# M103A.net
KiCad netlist of a schematic drawn in EAGLE
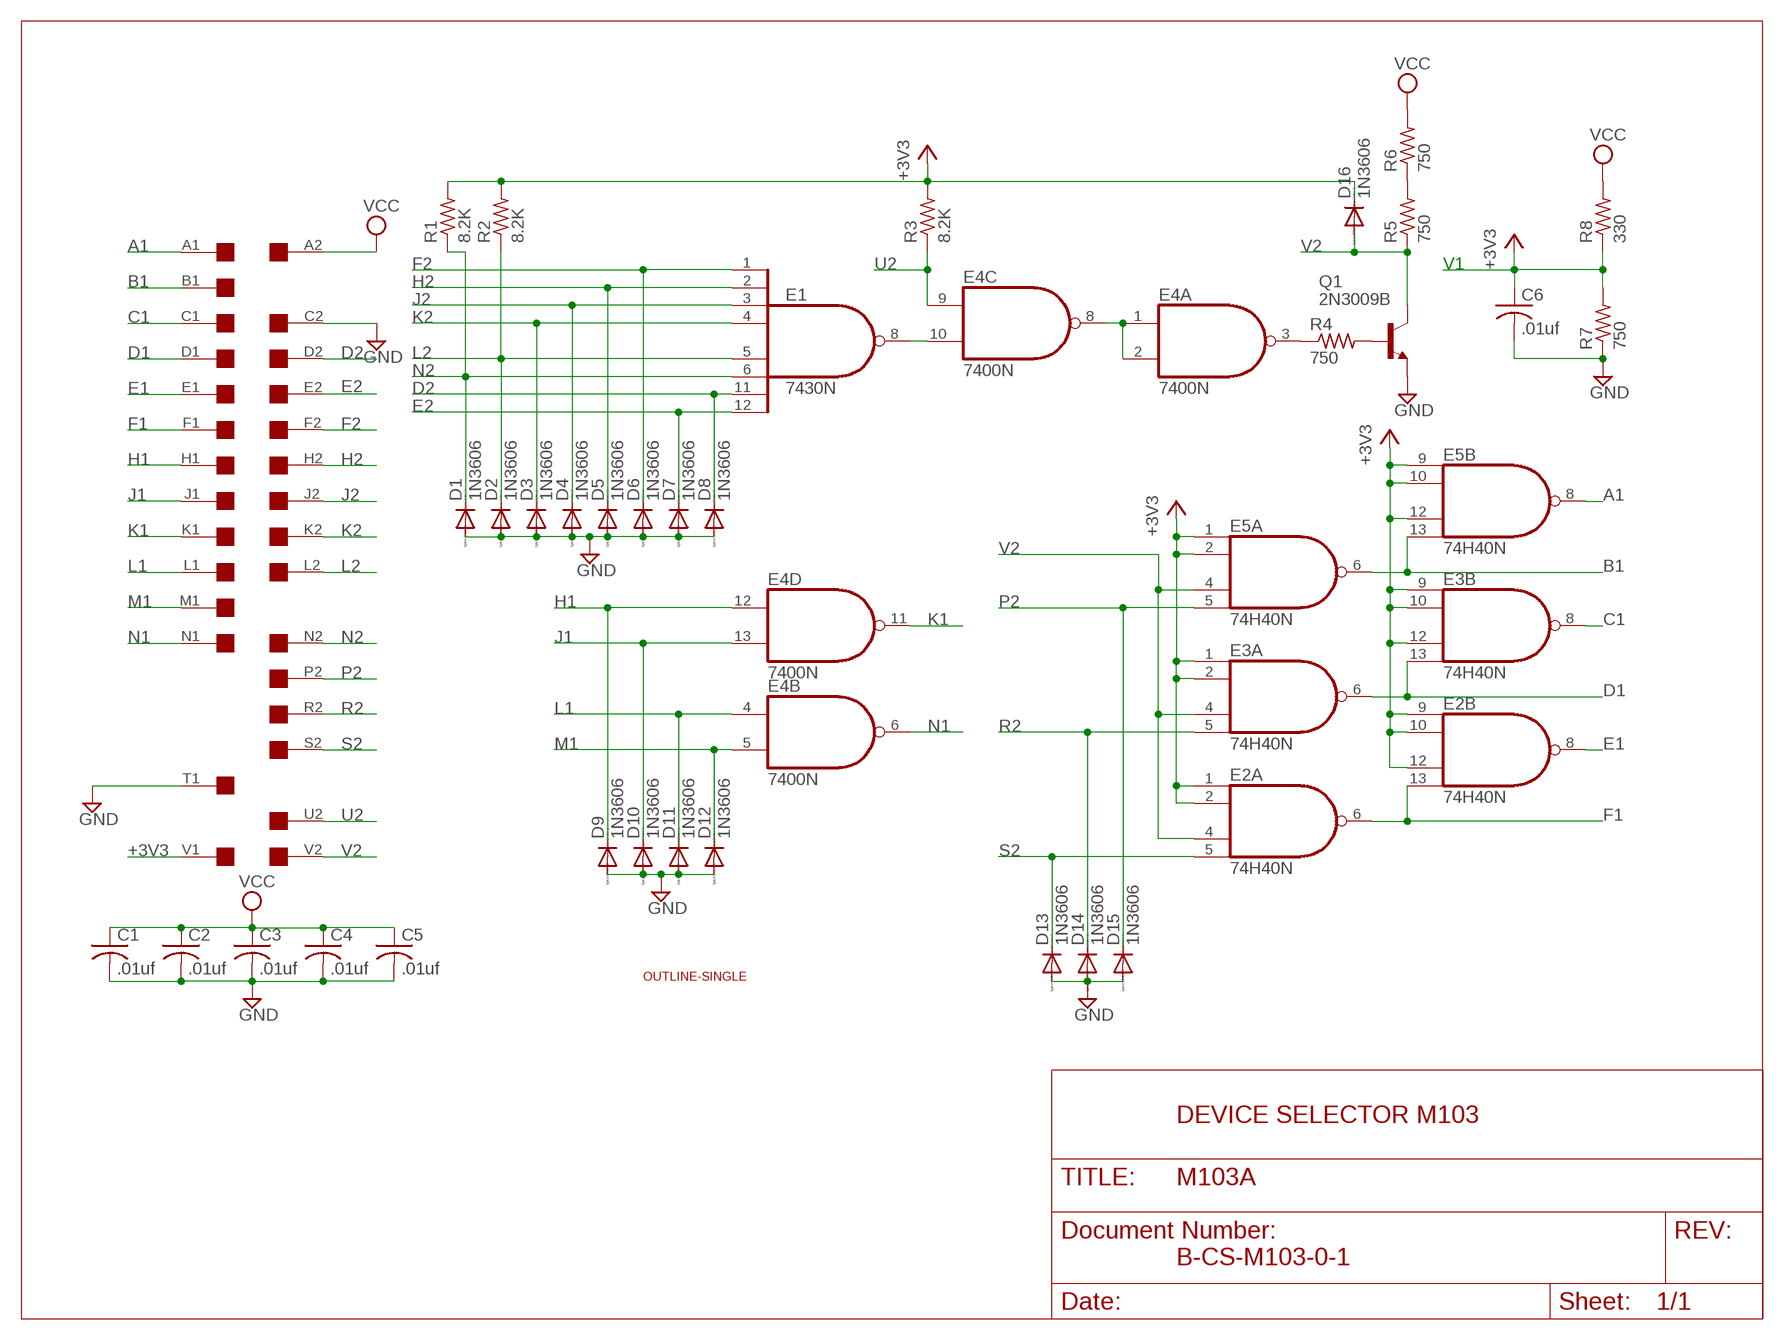
[diagram p0: schematic, sheet 1]

(export (version "E")
  (design (tool "Eeschema 10.0.6"))
  (components
    (comp (ref "C1")
      (value ".01uf")
      (footprint "eagle-import:C050-025X075")
      (libsource (lib "eagle-import") (part "C-US050-025X075"))
    )
    (comp (ref "C2")
      (value ".01uf")
      (footprint "eagle-import:C050-025X075")
      (libsource (lib "eagle-import") (part "C-US050-025X075"))
    )
    (comp (ref "C3")
      (value ".01uf")
      (footprint "eagle-import:C050-025X075")
      (libsource (lib "eagle-import") (part "C-US050-025X075"))
    )
    (comp (ref "C4")
      (value ".01uf")
      (footprint "eagle-import:C050-025X075")
      (libsource (lib "eagle-import") (part "C-US050-025X075"))
    )
    (comp (ref "C5")
      (value ".01uf")
      (footprint "eagle-import:C050-025X075")
      (libsource (lib "eagle-import") (part "C-US050-025X075"))
    )
    (comp (ref "C6")
      (value ".01uf")
      (footprint "eagle-import:C050-025X075")
      (libsource (lib "eagle-import") (part "C-US050-025X075"))
    )
    (comp (ref "D1")
      (value "1N3606")
      (footprint "eagle-import:DO35-10")
      (libsource (lib "eagle-import") (part "1N4148DO35-10"))
    )
    (comp (ref "D2")
      (value "1N3606")
      (footprint "eagle-import:DO35-10")
      (libsource (lib "eagle-import") (part "1N4148DO35-10"))
    )
    (comp (ref "D3")
      (value "1N3606")
      (footprint "eagle-import:DO35-10")
      (libsource (lib "eagle-import") (part "1N4148DO35-10"))
    )
    (comp (ref "D4")
      (value "1N3606")
      (footprint "eagle-import:DO35-10")
      (libsource (lib "eagle-import") (part "1N4148DO35-10"))
    )
    (comp (ref "D5")
      (value "1N3606")
      (footprint "eagle-import:DO35-10")
      (libsource (lib "eagle-import") (part "1N4148DO35-10"))
    )
    (comp (ref "D6")
      (value "1N3606")
      (footprint "eagle-import:DO35-10")
      (libsource (lib "eagle-import") (part "1N4148DO35-10"))
    )
    (comp (ref "D7")
      (value "1N3606")
      (footprint "eagle-import:DO35-10")
      (libsource (lib "eagle-import") (part "1N4148DO35-10"))
    )
    (comp (ref "D8")
      (value "1N3606")
      (footprint "eagle-import:DO35-10")
      (libsource (lib "eagle-import") (part "1N4148DO35-10"))
    )
    (comp (ref "D9")
      (value "1N3606")
      (footprint "eagle-import:DO35-10")
      (libsource (lib "eagle-import") (part "1N4148DO35-10"))
    )
    (comp (ref "D10")
      (value "1N3606")
      (footprint "eagle-import:DO35-10")
      (libsource (lib "eagle-import") (part "1N4148DO35-10"))
    )
    (comp (ref "D11")
      (value "1N3606")
      (footprint "eagle-import:DO35-10")
      (libsource (lib "eagle-import") (part "1N4148DO35-10"))
    )
    (comp (ref "D12")
      (value "1N3606")
      (footprint "eagle-import:DO35-10")
      (libsource (lib "eagle-import") (part "1N4148DO35-10"))
    )
    (comp (ref "D13")
      (value "1N3606")
      (footprint "eagle-import:DO35-10")
      (libsource (lib "eagle-import") (part "1N4148DO35-10"))
    )
    (comp (ref "D14")
      (value "1N3606")
      (footprint "eagle-import:DO35-10")
      (libsource (lib "eagle-import") (part "1N4148DO35-10"))
    )
    (comp (ref "D15")
      (value "1N3606")
      (footprint "eagle-import:DO35-10")
      (libsource (lib "eagle-import") (part "1N4148DO35-10"))
    )
    (comp (ref "D16")
      (value "1N3606")
      (footprint "eagle-import:DO35-10")
      (libsource (lib "eagle-import") (part "1N4148DO35-10"))
    )
    (comp (ref "E1")
      (value "7430N")
      (footprint "eagle-import:DIL14")
      (libsource (lib "eagle-import") (part "7430N"))
    )
    (comp (ref "E2")
      (value "74H40N")
      (footprint "eagle-import:DIL14")
      (libsource (lib "eagle-import") (part "7420NS"))
    )
    (comp (ref "E3")
      (value "74H40N")
      (footprint "eagle-import:DIL14")
      (libsource (lib "eagle-import") (part "7420NS"))
    )
    (comp (ref "E4")
      (value "7400N")
      (footprint "eagle-import:DIL14")
      (libsource (lib "eagle-import") (part "7400N"))
    )
    (comp (ref "E5")
      (value "74H40N")
      (footprint "eagle-import:DIL14")
      (libsource (lib "eagle-import") (part "7420NS"))
    )
    (comp (ref "Q1")
      (value "2N3009B")
      (footprint "eagle-import:TO39")
      (libsource (lib "eagle-import") (part "-NPN-TO39-EBC2N1613"))
    )
    (comp (ref "R1")
      (value "8.2K")
      (footprint "eagle-import:0207_10")
      (libsource (lib "eagle-import") (part "R-US_0207/10"))
    )
    (comp (ref "R2")
      (value "8.2K")
      (footprint "eagle-import:0207_10")
      (libsource (lib "eagle-import") (part "R-US_0207/10"))
    )
    (comp (ref "R3")
      (value "8.2K")
      (footprint "eagle-import:0207_10")
      (libsource (lib "eagle-import") (part "R-US_0207/10"))
    )
    (comp (ref "R4")
      (value "750")
      (footprint "eagle-import:0207_10")
      (libsource (lib "eagle-import") (part "R-US_0207/10"))
    )
    (comp (ref "R5")
      (value "750")
      (footprint "eagle-import:0207_10")
      (libsource (lib "eagle-import") (part "R-US_0207/10"))
    )
    (comp (ref "R6")
      (value "750")
      (footprint "eagle-import:0207_10")
      (libsource (lib "eagle-import") (part "R-US_0207/10"))
    )
    (comp (ref "R7")
      (value "750")
      (footprint "eagle-import:0207_10")
      (libsource (lib "eagle-import") (part "R-US_0207/10"))
    )
    (comp (ref "R8")
      (value "330")
      (footprint "eagle-import:0207_10")
      (libsource (lib "eagle-import") (part "R-US_0207/10"))
    )
    (comp (ref "U$8")
      (value "SINGLE")
      (footprint "eagle-import:EDGE-CON2")
      (libsource (lib "eagle-import") (part "SINGLE"))
    )
    (comp (ref "U$9")
      (value "OUTLINE-SINGLE")
      (footprint "eagle-import:SINGLE")
      (libsource (lib "eagle-import") (part "OUTLINE-SINGLE"))
    )
  )
  (nets
    (net (code "1") (name "+3V3") (class "Default")
      (node (ref "C6") (pin "1") (pinfunction "1_1") (pintype "passive"))
      (node (ref "D16") (pin "C") (pinfunction "C_C") (pintype "passive"))
      (node (ref "E2") (pin "1") (pinfunction "I0_1") (pintype "input"))
      (node (ref "E2") (pin "10") (pinfunction "I1_10") (pintype "input"))
      (node (ref "E2") (pin "12") (pinfunction "I2_12") (pintype "input"))
      (node (ref "E2") (pin "2") (pinfunction "I1_2") (pintype "input"))
      (node (ref "E2") (pin "9") (pinfunction "I0_9") (pintype "input"))
      (node (ref "E3") (pin "1") (pinfunction "I0_1") (pintype "input"))
      (node (ref "E3") (pin "10") (pinfunction "I1_10") (pintype "input"))
      (node (ref "E3") (pin "12") (pinfunction "I2_12") (pintype "input"))
      (node (ref "E3") (pin "2") (pinfunction "I1_2") (pintype "input"))
      (node (ref "E3") (pin "9") (pinfunction "I0_9") (pintype "input"))
      (node (ref "E5") (pin "1") (pinfunction "I0_1") (pintype "input"))
      (node (ref "E5") (pin "10") (pinfunction "I1_10") (pintype "input"))
      (node (ref "E5") (pin "12") (pinfunction "I2_12") (pintype "input"))
      (node (ref "E5") (pin "2") (pinfunction "I1_2") (pintype "input"))
      (node (ref "E5") (pin "9") (pinfunction "I0_9") (pintype "input"))
      (node (ref "R1") (pin "2") (pinfunction "2_2") (pintype "passive"))
      (node (ref "R2") (pin "2") (pinfunction "2_2") (pintype "passive"))
      (node (ref "R3") (pin "2") (pinfunction "2_2") (pintype "passive"))
      (node (ref "R7") (pin "2") (pinfunction "2_2") (pintype "passive"))
      (node (ref "R8") (pin "1") (pinfunction "1_1") (pintype "passive"))
      (node (ref "U$8") (pin "V1") (pinfunction "1_V1") (pintype "bidirectional"))
    )
    (net (code "2") (name "/A1") (class "Default")
      (node (ref "E5") (pin "8") (pinfunction "O_8") (pintype "output"))
      (node (ref "U$8") (pin "A1") (pinfunction "1_A1") (pintype "bidirectional"))
    )
    (net (code "3") (name "/B1") (class "Default")
      (node (ref "E5") (pin "13") (pinfunction "I3_13") (pintype "input"))
      (node (ref "E5") (pin "6") (pinfunction "O_6") (pintype "output"))
      (node (ref "U$8") (pin "B1") (pinfunction "1_B1") (pintype "bidirectional"))
    )
    (net (code "4") (name "/C1") (class "Default")
      (node (ref "E3") (pin "8") (pinfunction "O_8") (pintype "output"))
      (node (ref "U$8") (pin "C1") (pinfunction "1_C1") (pintype "bidirectional"))
    )
    (net (code "5") (name "/D1") (class "Default")
      (node (ref "E3") (pin "13") (pinfunction "I3_13") (pintype "input"))
      (node (ref "E3") (pin "6") (pinfunction "O_6") (pintype "output"))
      (node (ref "U$8") (pin "D1") (pinfunction "1_D1") (pintype "bidirectional"))
    )
    (net (code "6") (name "/D2") (class "Default")
      (node (ref "D8") (pin "C") (pinfunction "C_C") (pintype "passive"))
      (node (ref "E1") (pin "11") (pinfunction "I6_11") (pintype "input"))
      (node (ref "U$8") (pin "D2") (pinfunction "1_D2") (pintype "bidirectional"))
    )
    (net (code "7") (name "/E1") (class "Default")
      (node (ref "E2") (pin "8") (pinfunction "O_8") (pintype "output"))
      (node (ref "U$8") (pin "E1") (pinfunction "1_E1") (pintype "bidirectional"))
    )
    (net (code "8") (name "/E2") (class "Default")
      (node (ref "D7") (pin "C") (pinfunction "C_C") (pintype "passive"))
      (node (ref "E1") (pin "12") (pinfunction "I7_12") (pintype "input"))
      (node (ref "U$8") (pin "E2") (pinfunction "1_E2") (pintype "bidirectional"))
    )
    (net (code "9") (name "/F1") (class "Default")
      (node (ref "E2") (pin "13") (pinfunction "I3_13") (pintype "input"))
      (node (ref "E2") (pin "6") (pinfunction "O_6") (pintype "output"))
      (node (ref "U$8") (pin "F1") (pinfunction "1_F1") (pintype "bidirectional"))
    )
    (net (code "10") (name "/F2") (class "Default")
      (node (ref "D6") (pin "C") (pinfunction "C_C") (pintype "passive"))
      (node (ref "E1") (pin "1") (pinfunction "I0_1") (pintype "input"))
      (node (ref "U$8") (pin "F2") (pinfunction "1_F2") (pintype "bidirectional"))
    )
    (net (code "11") (name "/H1") (class "Default")
      (node (ref "D9") (pin "C") (pinfunction "C_C") (pintype "passive"))
      (node (ref "E4") (pin "12") (pinfunction "I0_12") (pintype "input"))
      (node (ref "U$8") (pin "H1") (pinfunction "1_H1") (pintype "bidirectional"))
    )
    (net (code "12") (name "/H2") (class "Default")
      (node (ref "D5") (pin "C") (pinfunction "C_C") (pintype "passive"))
      (node (ref "E1") (pin "2") (pinfunction "I1_2") (pintype "input"))
      (node (ref "U$8") (pin "H2") (pinfunction "1_H2") (pintype "bidirectional"))
    )
    (net (code "13") (name "/J1") (class "Default")
      (node (ref "D10") (pin "C") (pinfunction "C_C") (pintype "passive"))
      (node (ref "E4") (pin "13") (pinfunction "I1_13") (pintype "input"))
      (node (ref "U$8") (pin "J1") (pinfunction "1_J1") (pintype "bidirectional"))
    )
    (net (code "14") (name "/J2") (class "Default")
      (node (ref "D4") (pin "C") (pinfunction "C_C") (pintype "passive"))
      (node (ref "E1") (pin "3") (pinfunction "I2_3") (pintype "input"))
      (node (ref "U$8") (pin "J2") (pinfunction "1_J2") (pintype "bidirectional"))
    )
    (net (code "15") (name "/K1") (class "Default")
      (node (ref "E4") (pin "11") (pinfunction "O_11") (pintype "output"))
      (node (ref "U$8") (pin "K1") (pinfunction "1_K1") (pintype "bidirectional"))
    )
    (net (code "16") (name "/K2") (class "Default")
      (node (ref "D3") (pin "C") (pinfunction "C_C") (pintype "passive"))
      (node (ref "E1") (pin "4") (pinfunction "I3_4") (pintype "input"))
      (node (ref "U$8") (pin "K2") (pinfunction "1_K2") (pintype "bidirectional"))
    )
    (net (code "17") (name "/L1") (class "Default")
      (node (ref "D11") (pin "C") (pinfunction "C_C") (pintype "passive"))
      (node (ref "E4") (pin "4") (pinfunction "I0_4") (pintype "input"))
      (node (ref "U$8") (pin "L1") (pinfunction "1_L1") (pintype "bidirectional"))
    )
    (net (code "18") (name "/L2") (class "Default")
      (node (ref "D2") (pin "C") (pinfunction "C_C") (pintype "passive"))
      (node (ref "E1") (pin "5") (pinfunction "I4_5") (pintype "input"))
      (node (ref "R2") (pin "1") (pinfunction "1_1") (pintype "passive"))
      (node (ref "U$8") (pin "L2") (pinfunction "1_L2") (pintype "bidirectional"))
    )
    (net (code "19") (name "/M1") (class "Default")
      (node (ref "D12") (pin "C") (pinfunction "C_C") (pintype "passive"))
      (node (ref "E4") (pin "5") (pinfunction "I1_5") (pintype "input"))
      (node (ref "U$8") (pin "M1") (pinfunction "1_M1") (pintype "bidirectional"))
    )
    (net (code "20") (name "/N1") (class "Default")
      (node (ref "E4") (pin "6") (pinfunction "O_6") (pintype "output"))
      (node (ref "U$8") (pin "N1") (pinfunction "1_N1") (pintype "bidirectional"))
    )
    (net (code "21") (name "/N2") (class "Default")
      (node (ref "D1") (pin "C") (pinfunction "C_C") (pintype "passive"))
      (node (ref "E1") (pin "6") (pinfunction "I5_6") (pintype "input"))
      (node (ref "R1") (pin "1") (pinfunction "1_1") (pintype "passive"))
      (node (ref "U$8") (pin "N2") (pinfunction "1_N2") (pintype "bidirectional"))
    )
    (net (code "22") (name "/P2") (class "Default")
      (node (ref "D15") (pin "C") (pinfunction "C_C") (pintype "passive"))
      (node (ref "E5") (pin "5") (pinfunction "I3_5") (pintype "input"))
      (node (ref "U$8") (pin "P2") (pinfunction "1_P2") (pintype "bidirectional"))
    )
    (net (code "23") (name "/R2") (class "Default")
      (node (ref "D14") (pin "C") (pinfunction "C_C") (pintype "passive"))
      (node (ref "E3") (pin "5") (pinfunction "I3_5") (pintype "input"))
      (node (ref "U$8") (pin "R2") (pinfunction "1_R2") (pintype "bidirectional"))
    )
    (net (code "24") (name "/S2") (class "Default")
      (node (ref "D13") (pin "C") (pinfunction "C_C") (pintype "passive"))
      (node (ref "E2") (pin "5") (pinfunction "I3_5") (pintype "input"))
      (node (ref "U$8") (pin "S2") (pinfunction "1_S2") (pintype "bidirectional"))
    )
    (net (code "25") (name "/U2") (class "Default")
      (node (ref "E4") (pin "9") (pinfunction "I0_9") (pintype "input"))
      (node (ref "R3") (pin "1") (pinfunction "1_1") (pintype "passive"))
      (node (ref "U$8") (pin "U2") (pinfunction "1_U2") (pintype "bidirectional"))
    )
    (net (code "26") (name "/V2") (class "Default")
      (node (ref "D16") (pin "A") (pinfunction "A_A") (pintype "passive"))
      (node (ref "E2") (pin "4") (pinfunction "I2_4") (pintype "input"))
      (node (ref "E3") (pin "4") (pinfunction "I2_4") (pintype "input"))
      (node (ref "E5") (pin "4") (pinfunction "I2_4") (pintype "input"))
      (node (ref "Q1") (pin "3") (pinfunction "C_3") (pintype "passive"))
      (node (ref "R5") (pin "1") (pinfunction "1_1") (pintype "passive"))
      (node (ref "U$8") (pin "V2") (pinfunction "1_V2") (pintype "bidirectional"))
    )
    (net (code "27") (name "GND") (class "Default")
      (node (ref "C1") (pin "2") (pinfunction "2_2") (pintype "passive"))
      (node (ref "C2") (pin "2") (pinfunction "2_2") (pintype "passive"))
      (node (ref "C3") (pin "2") (pinfunction "2_2") (pintype "passive"))
      (node (ref "C4") (pin "2") (pinfunction "2_2") (pintype "passive"))
      (node (ref "C5") (pin "2") (pinfunction "2_2") (pintype "passive"))
      (node (ref "C6") (pin "2") (pinfunction "2_2") (pintype "passive"))
      (node (ref "D1") (pin "A") (pinfunction "A_A") (pintype "passive"))
      (node (ref "D10") (pin "A") (pinfunction "A_A") (pintype "passive"))
      (node (ref "D11") (pin "A") (pinfunction "A_A") (pintype "passive"))
      (node (ref "D12") (pin "A") (pinfunction "A_A") (pintype "passive"))
      (node (ref "D13") (pin "A") (pinfunction "A_A") (pintype "passive"))
      (node (ref "D14") (pin "A") (pinfunction "A_A") (pintype "passive"))
      (node (ref "D15") (pin "A") (pinfunction "A_A") (pintype "passive"))
      (node (ref "D2") (pin "A") (pinfunction "A_A") (pintype "passive"))
      (node (ref "D3") (pin "A") (pinfunction "A_A") (pintype "passive"))
      (node (ref "D4") (pin "A") (pinfunction "A_A") (pintype "passive"))
      (node (ref "D5") (pin "A") (pinfunction "A_A") (pintype "passive"))
      (node (ref "D6") (pin "A") (pinfunction "A_A") (pintype "passive"))
      (node (ref "D7") (pin "A") (pinfunction "A_A") (pintype "passive"))
      (node (ref "D8") (pin "A") (pinfunction "A_A") (pintype "passive"))
      (node (ref "D9") (pin "A") (pinfunction "A_A") (pintype "passive"))
      (node (ref "Q1") (pin "1") (pinfunction "E_1") (pintype "passive"))
      (node (ref "R7") (pin "1") (pinfunction "1_1") (pintype "passive"))
      (node (ref "U$8") (pin "C2") (pinfunction "1_C2") (pintype "bidirectional"))
      (node (ref "U$8") (pin "T1") (pinfunction "1_T1") (pintype "bidirectional"))
    )
    (net (code "28") (name "Net-(E1A-O)") (class "Default")
      (node (ref "E1") (pin "8") (pinfunction "O_8") (pintype "output"))
      (node (ref "E4") (pin "10") (pinfunction "I1_10") (pintype "input"))
    )
    (net (code "29") (name "Net-(E4A-I0)") (class "Default")
      (node (ref "E4") (pin "1") (pinfunction "I0_1") (pintype "input"))
      (node (ref "E4") (pin "2") (pinfunction "I1_2") (pintype "input"))
      (node (ref "E4") (pin "8") (pinfunction "O_8") (pintype "output"))
    )
    (net (code "30") (name "Net-(E4A-O)") (class "Default")
      (node (ref "E4") (pin "3") (pinfunction "O_3") (pintype "output"))
      (node (ref "R4") (pin "1") (pinfunction "1_1") (pintype "passive"))
    )
    (net (code "31") (name "Net-(Q1-B)") (class "Default")
      (node (ref "Q1") (pin "2") (pinfunction "B_2") (pintype "passive"))
      (node (ref "R4") (pin "2") (pinfunction "2_2") (pintype "passive"))
    )
    (net (code "32") (name "Net-(R5-Pad2)") (class "Default")
      (node (ref "R5") (pin "2") (pinfunction "2_2") (pintype "passive"))
      (node (ref "R6") (pin "1") (pinfunction "1_1") (pintype "passive"))
    )
    (net (code "33") (name "VCC") (class "Default")
      (node (ref "C1") (pin "1") (pinfunction "1_1") (pintype "passive"))
      (node (ref "C2") (pin "1") (pinfunction "1_1") (pintype "passive"))
      (node (ref "C3") (pin "1") (pinfunction "1_1") (pintype "passive"))
      (node (ref "C4") (pin "1") (pinfunction "1_1") (pintype "passive"))
      (node (ref "C5") (pin "1") (pinfunction "1_1") (pintype "passive"))
      (node (ref "R6") (pin "2") (pinfunction "2_2") (pintype "passive"))
      (node (ref "R8") (pin "2") (pinfunction "2_2") (pintype "passive"))
      (node (ref "U$8") (pin "A2") (pinfunction "1_A2") (pintype "bidirectional"))
    )
  )
)
